# TOP_PCB_dbl.net
KiCad netlist of a schematic drawn in EAGLE
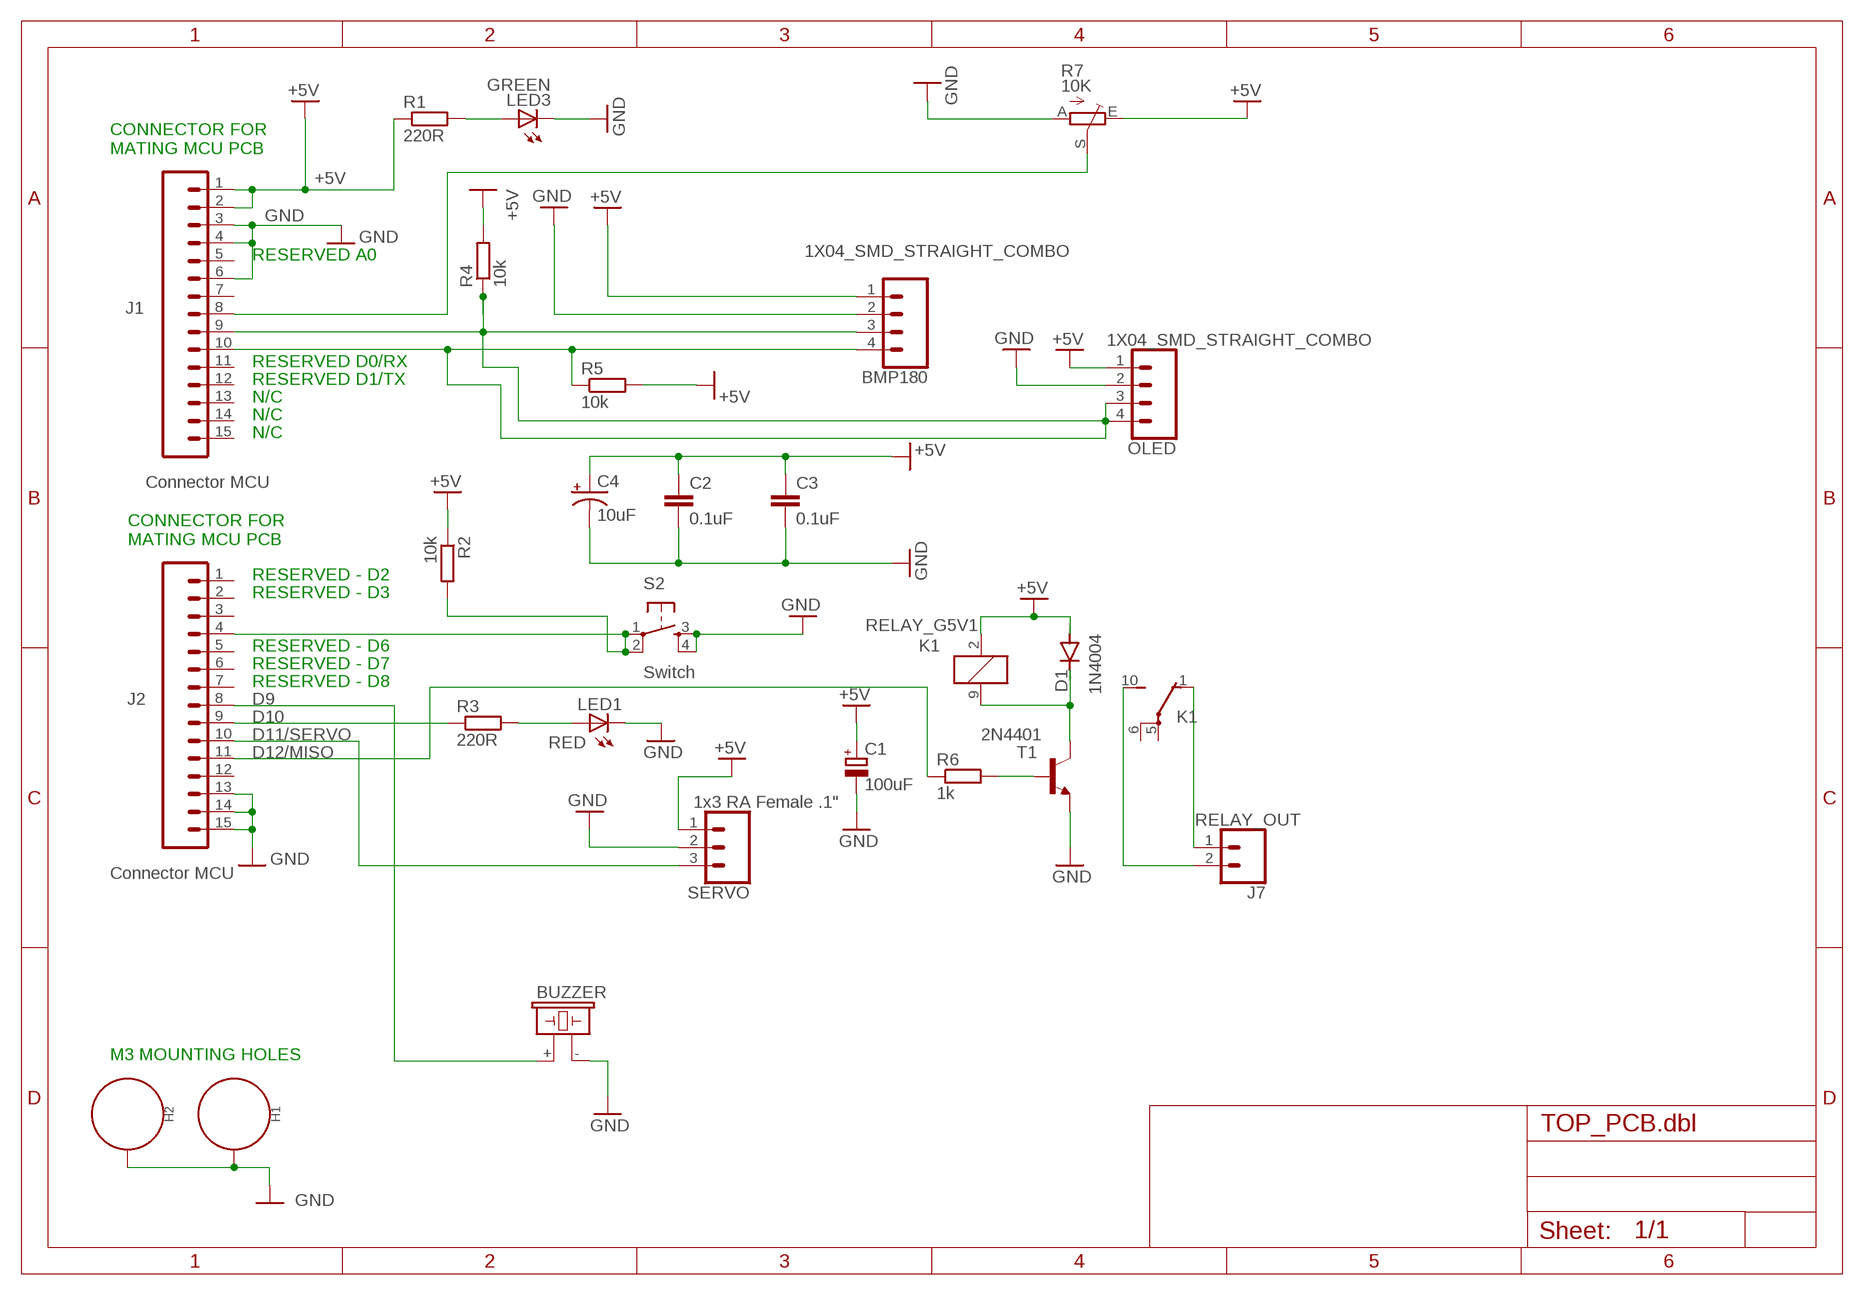
[diagram p0: schematic, sheet 1]

(export (version "E")
  (design (tool "Eeschema 10.0.6"))
  (components
    (comp (ref "BMP180")
      (value "1X04_SMD_STRAIGHT_COMBO")
      (footprint "eagle-import:1X04_LONGPADS")
      (libsource (lib "eagle-import") (part "CONN_04LONGPADS"))
    )
    (comp (ref "BUZZER")
      (value "EL311_ATMEGA_INTRO_TSC033_V1_BUZZER_F/CM12P")
      (footprint "eagle-import:EL311_ATMEGA_INTRO_TSC033_V1_BUZZER_F_CM12P")
      (libsource (lib "eagle-import") (part "EL311_ATMEGA_INTRO_TSC033_V1_BUZZER_F/CM12P"))
    )
    (comp (ref "C1")
      (value "100uF")
      (footprint "eagle-import:ELECTROLYTIC_CAP_RCL_E3,5-8")
      (libsource (lib "eagle-import") (part "RCL_CPOL-EUE3.5-8"))
    )
    (comp (ref "C2")
      (value "0.1uF")
      (footprint "eagle-import:C2.5-2")
      (libsource (lib "eagle-import") (part "C2.5/2"))
    )
    (comp (ref "C3")
      (value "0.1uF")
      (footprint "eagle-import:C2.5-2")
      (libsource (lib "eagle-import") (part "C2.5/2"))
    )
    (comp (ref "C4")
      (value "10uF")
      (footprint "eagle-import:E3,5-8")
      (libsource (lib "eagle-import") (part "CPOL-USE3.5-8"))
    )
    (comp (ref "D1")
      (value "1N4004")
      (footprint "eagle-import:DO41-10")
      (libsource (lib "eagle-import") (part "1N4004"))
    )
    (comp (ref "H1")
      (value "STANDOFF_ELECTRICAL")
      (footprint "eagle-import:STANDOFF-ELECTRICAL")
      (libsource (lib "eagle-import") (part "STANDOFF_ELECTRICAL"))
    )
    (comp (ref "H2")
      (value "STANDOFF_ELECTRICAL")
      (footprint "eagle-import:STANDOFF-ELECTRICAL")
      (libsource (lib "eagle-import") (part "STANDOFF_ELECTRICAL"))
    )
    (comp (ref "J1")
      (value "Connector MCU")
      (footprint "eagle-import:1X15")
      (libsource (lib "eagle-import") (part "CONN_15"))
    )
    (comp (ref "J2")
      (value "Connector MCU")
      (footprint "eagle-import:1X15")
      (libsource (lib "eagle-import") (part "CONN_15"))
    )
    (comp (ref "J7")
      (value "RELAY_OUT")
      (footprint "eagle-import:SPARKFUN-CONNECTORS_1X02")
      (libsource (lib "eagle-import") (part "SPARKFUN-CONNECTORS_CONN_02"))
    )
    (comp (ref "K1")
      (value "RELAY_G5V1")
      (footprint "eagle-import:RELAY_G5V1")
      (fields (field (name "MPN") "G5V-1-DC24"))
      (libsource (lib "eagle-import") (part "RELAY_G5V1"))
    )
    (comp (ref "LED1")
      (value "RED")
      (footprint "eagle-import:ADAFRUIT_LED3MM")
      (libsource (lib "eagle-import") (part "ADAFRUIT_LED3MM"))
    )
    (comp (ref "LED3")
      (value "GREEN")
      (footprint "eagle-import:LED3MM")
      (libsource (lib "eagle-import") (part "LED3MM"))
    )
    (comp (ref "OLED")
      (value "1X04_SMD_STRAIGHT_COMBO")
      (footprint "eagle-import:1X04_LONGPADS")
      (libsource (lib "eagle-import") (part "CONN_04LONGPADS"))
    )
    (comp (ref "R1")
      (value "220R")
      (footprint "eagle-import:0207_10")
      (libsource (lib "eagle-import") (part "R-EU_0207/10"))
    )
    (comp (ref "R2")
      (value "10k")
      (footprint "eagle-import:0207_10")
      (libsource (lib "eagle-import") (part "R-EU_0207/10"))
    )
    (comp (ref "R3")
      (value "220R")
      (footprint "eagle-import:0207_10")
      (libsource (lib "eagle-import") (part "R-EU_0207/10"))
    )
    (comp (ref "R4")
      (value "10k")
      (footprint "eagle-import:0207_10")
      (libsource (lib "eagle-import") (part "R-EU_0207/10"))
    )
    (comp (ref "R5")
      (value "10k")
      (footprint "eagle-import:0207_10")
      (libsource (lib "eagle-import") (part "R-EU_0207/10"))
    )
    (comp (ref "R6")
      (value "1k")
      (footprint "eagle-import:0207_10")
      (libsource (lib "eagle-import") (part "R-EU_0207/10"))
    )
    (comp (ref "R7")
      (value "10K")
      (footprint "eagle-import:RS3")
      (libsource (lib "eagle-import") (part "TRIM_EU-RS3"))
    )
    (comp (ref "S2")
      (value "Switch")
      (footprint "eagle-import:EL311-ROBOT_SPARKFUN-ELECTROMECHANICAL_TACTILE-PTH")
      (libsource (lib "eagle-import") (part "EL311-ROBOT_SPARKFUN-ELECTROMECHANICAL_TAC_SWITCHPTH"))
    )
    (comp (ref "SERVO")
      (value "1x3 RA Female .1\"")
      (footprint "eagle-import:1X03_LONGPADS")
      (libsource (lib "eagle-import") (part "CONN_03LONGPADS"))
    )
    (comp (ref "T1")
      (value "2N4401")
      (footprint "eagle-import:TO92-EBC")
      (libsource (lib "eagle-import") (part "-NPN-TO92-EBC"))
    )
  )
  (nets
    (net (code "1") (name "+5V") (class "Default")
      (node (ref "BMP180") (pin "1") (pinfunction "1_1") (pintype "passive"))
      (node (ref "C1") (pin "+") (pinfunction "+_+") (pintype "passive"))
      (node (ref "C2") (pin "1") (pinfunction "1_1") (pintype "passive"))
      (node (ref "C3") (pin "1") (pinfunction "1_1") (pintype "passive"))
      (node (ref "C4") (pin "+") (pinfunction "+_+") (pintype "passive"))
      (node (ref "D1") (pin "A") (pinfunction "A_A") (pintype "passive"))
      (node (ref "J1") (pin "1") (pinfunction "1_1") (pintype "passive"))
      (node (ref "J1") (pin "2") (pinfunction "2_2") (pintype "passive"))
      (node (ref "K1") (pin "2") (pinfunction "1_2") (pintype "passive"))
      (node (ref "OLED") (pin "1") (pinfunction "1_1") (pintype "passive"))
      (node (ref "R1") (pin "1") (pinfunction "1_1") (pintype "passive"))
      (node (ref "R2") (pin "1") (pinfunction "1_1") (pintype "passive"))
      (node (ref "R4") (pin "2") (pinfunction "2_2") (pintype "passive"))
      (node (ref "R5") (pin "2") (pinfunction "2_2") (pintype "passive"))
      (node (ref "R7") (pin "E") (pinfunction "E_E") (pintype "passive"))
      (node (ref "SERVO") (pin "1") (pinfunction "1_1") (pintype "passive"))
    )
    (net (code "2") (name "/D9") (class "Default")
      (node (ref "BUZZER") (pin "+") (pinfunction "1_+") (pintype "passive"))
      (node (ref "J2") (pin "8") (pinfunction "8_8") (pintype "passive"))
    )
    (net (code "3") (name "/D10") (class "Default")
      (node (ref "J2") (pin "9") (pinfunction "9_9") (pintype "passive"))
      (node (ref "R3") (pin "1") (pinfunction "1_1") (pintype "passive"))
    )
    (net (code "4") (name "/D11{slash}SERVO") (class "Default")
      (node (ref "J2") (pin "10") (pinfunction "10_10") (pintype "passive"))
      (node (ref "SERVO") (pin "3") (pinfunction "3_3") (pintype "passive"))
    )
    (net (code "5") (name "/D12{slash}MISO") (class "Default")
      (node (ref "J2") (pin "11") (pinfunction "11_11") (pintype "passive"))
      (node (ref "R6") (pin "1") (pinfunction "1_1") (pintype "passive"))
    )
    (net (code "6") (name "GND") (class "Default")
      (node (ref "BMP180") (pin "2") (pinfunction "2_2") (pintype "passive"))
      (node (ref "BUZZER") (pin "-") (pinfunction "2_-") (pintype "passive"))
      (node (ref "C1") (pin "-") (pinfunction "-_-") (pintype "passive"))
      (node (ref "C2") (pin "2") (pinfunction "2_2") (pintype "passive"))
      (node (ref "C3") (pin "2") (pinfunction "2_2") (pintype "passive"))
      (node (ref "C4") (pin "-") (pinfunction "-_-") (pintype "passive"))
      (node (ref "H1") (pin "P1") (pinfunction "P$1_P1") (pintype "bidirectional"))
      (node (ref "H2") (pin "P1") (pinfunction "P$1_P1") (pintype "bidirectional"))
      (node (ref "J1") (pin "3") (pinfunction "3_3") (pintype "passive"))
      (node (ref "J1") (pin "4") (pinfunction "4_4") (pintype "passive"))
      (node (ref "J1") (pin "6") (pinfunction "6_6") (pintype "passive"))
      (node (ref "J2") (pin "13") (pinfunction "13_13") (pintype "passive"))
      (node (ref "J2") (pin "14") (pinfunction "14_14") (pintype "passive"))
      (node (ref "J2") (pin "15") (pinfunction "15_15") (pintype "passive"))
      (node (ref "LED1") (pin "K") (pinfunction "C_K") (pintype "passive"))
      (node (ref "LED3") (pin "K") (pinfunction "C_K") (pintype "passive"))
      (node (ref "OLED") (pin "2") (pinfunction "2_2") (pintype "passive"))
      (node (ref "R7") (pin "A") (pinfunction "A_A") (pintype "passive"))
      (node (ref "S2") (pin "3") (pinfunction "3_3") (pintype "passive"))
      (node (ref "S2") (pin "4") (pinfunction "4_4") (pintype "passive"))
      (node (ref "SERVO") (pin "2") (pinfunction "2_2") (pintype "passive"))
      (node (ref "T1") (pin "E") (pinfunction "E_E") (pintype "passive"))
    )
    (net (code "7") (name "Net-(BMP180-Pad3)") (class "Default")
      (node (ref "BMP180") (pin "3") (pinfunction "3_3") (pintype "passive"))
      (node (ref "BMP180") (pin "4") (pinfunction "4_4") (pintype "passive"))
      (node (ref "J1") (pin "10") (pinfunction "10_10") (pintype "passive"))
      (node (ref "J1") (pin "9") (pinfunction "9_9") (pintype "passive"))
      (node (ref "OLED") (pin "3") (pinfunction "3_3") (pintype "passive"))
      (node (ref "OLED") (pin "4") (pinfunction "4_4") (pintype "passive"))
      (node (ref "R4") (pin "1") (pinfunction "1_1") (pintype "passive"))
      (node (ref "R5") (pin "1") (pinfunction "1_1") (pintype "passive"))
    )
    (net (code "8") (name "Net-(J1-Pad8)") (class "Default")
      (node (ref "J1") (pin "8") (pinfunction "8_8") (pintype "passive"))
      (node (ref "R7") (pin "S") (pinfunction "S_S") (pintype "passive"))
    )
    (net (code "9") (name "Net-(J2-Pad4)") (class "Default")
      (node (ref "J2") (pin "4") (pinfunction "4_4") (pintype "passive"))
      (node (ref "R2") (pin "2") (pinfunction "2_2") (pintype "passive"))
      (node (ref "S2") (pin "1") (pinfunction "1_1") (pintype "passive"))
      (node (ref "S2") (pin "2") (pinfunction "2_2") (pintype "passive"))
    )
    (net (code "10") (name "Net-(K1A-2)") (class "Default")
      (node (ref "D1") (pin "C") (pinfunction "C_C") (pintype "passive"))
      (node (ref "K1") (pin "9") (pinfunction "2_9") (pintype "passive"))
      (node (ref "T1") (pin "C") (pinfunction "C_C") (pintype "passive"))
    )
    (net (code "11") (name "Net-(K1B-O)") (class "Default")
      (node (ref "J7") (pin "1") (pinfunction "1_1") (pintype "passive"))
      (node (ref "K1") (pin "1") (pinfunction "O_1") (pintype "passive"))
    )
    (net (code "12") (name "Net-(K1B-S)") (class "Default")
      (node (ref "J7") (pin "2") (pinfunction "2_2") (pintype "passive"))
      (node (ref "K1") (pin "10") (pinfunction "S_10") (pintype "passive"))
    )
    (net (code "13") (name "Net-(LED1-PadA)") (class "Default")
      (node (ref "LED1") (pin "A") (pinfunction "A_A") (pintype "passive"))
      (node (ref "R3") (pin "2") (pinfunction "2_2") (pintype "passive"))
    )
    (net (code "14") (name "Net-(LED3-PadA)") (class "Default")
      (node (ref "LED3") (pin "A") (pinfunction "A_A") (pintype "passive"))
      (node (ref "R1") (pin "2") (pinfunction "2_2") (pintype "passive"))
    )
    (net (code "15") (name "Net-(R6-Pad2)") (class "Default")
      (node (ref "R6") (pin "2") (pinfunction "2_2") (pintype "passive"))
      (node (ref "T1") (pin "B") (pinfunction "B_B") (pintype "passive"))
    )
    (net (code "16") (name "unconnected-(J1-Pad5)") (class "Default")
      (node (ref "J1") (pin "5") (pinfunction "5_5") (pintype "passive"))
    )
    (net (code "17") (name "unconnected-(J1-Pad7)") (class "Default")
      (node (ref "J1") (pin "7") (pinfunction "7_7") (pintype "passive"))
    )
    (net (code "18") (name "unconnected-(J1-Pad11)") (class "Default")
      (node (ref "J1") (pin "11") (pinfunction "11_11") (pintype "passive"))
    )
    (net (code "19") (name "unconnected-(J1-Pad12)") (class "Default")
      (node (ref "J1") (pin "12") (pinfunction "12_12") (pintype "passive"))
    )
    (net (code "20") (name "unconnected-(J1-Pad13)") (class "Default")
      (node (ref "J1") (pin "13") (pinfunction "13_13") (pintype "passive"))
    )
    (net (code "21") (name "unconnected-(J1-Pad14)") (class "Default")
      (node (ref "J1") (pin "14") (pinfunction "14_14") (pintype "passive"))
    )
    (net (code "22") (name "unconnected-(J1-Pad15)") (class "Default")
      (node (ref "J1") (pin "15") (pinfunction "15_15") (pintype "passive"))
    )
    (net (code "23") (name "unconnected-(J2-Pad1)") (class "Default")
      (node (ref "J2") (pin "1") (pinfunction "1_1") (pintype "passive"))
    )
    (net (code "24") (name "unconnected-(J2-Pad2)") (class "Default")
      (node (ref "J2") (pin "2") (pinfunction "2_2") (pintype "passive"))
    )
    (net (code "25") (name "unconnected-(J2-Pad3)") (class "Default")
      (node (ref "J2") (pin "3") (pinfunction "3_3") (pintype "passive"))
    )
    (net (code "26") (name "unconnected-(J2-Pad5)") (class "Default")
      (node (ref "J2") (pin "5") (pinfunction "5_5") (pintype "passive"))
    )
    (net (code "27") (name "unconnected-(J2-Pad6)") (class "Default")
      (node (ref "J2") (pin "6") (pinfunction "6_6") (pintype "passive"))
    )
    (net (code "28") (name "unconnected-(J2-Pad7)") (class "Default")
      (node (ref "J2") (pin "7") (pinfunction "7_7") (pintype "passive"))
    )
    (net (code "29") (name "unconnected-(J2-Pad12)") (class "Default")
      (node (ref "J2") (pin "12") (pinfunction "12_12") (pintype "passive"))
    )
    (net (code "30") (name "unconnected-(K1B-P-Pad5)") (class "Default")
      (node (ref "K1") (pin "5") (pinfunction "P_5") (pintype "passive"))
    )
    (net (code "31") (name "unconnected-(K1B-P-Pad6)") (class "Default")
      (node (ref "K1") (pin "6") (pinfunction "P_6") (pintype "passive"))
    )
  )
)
